# BLE_v1_0_prater_mod.net
KiCad netlist of a schematic drawn in EAGLE
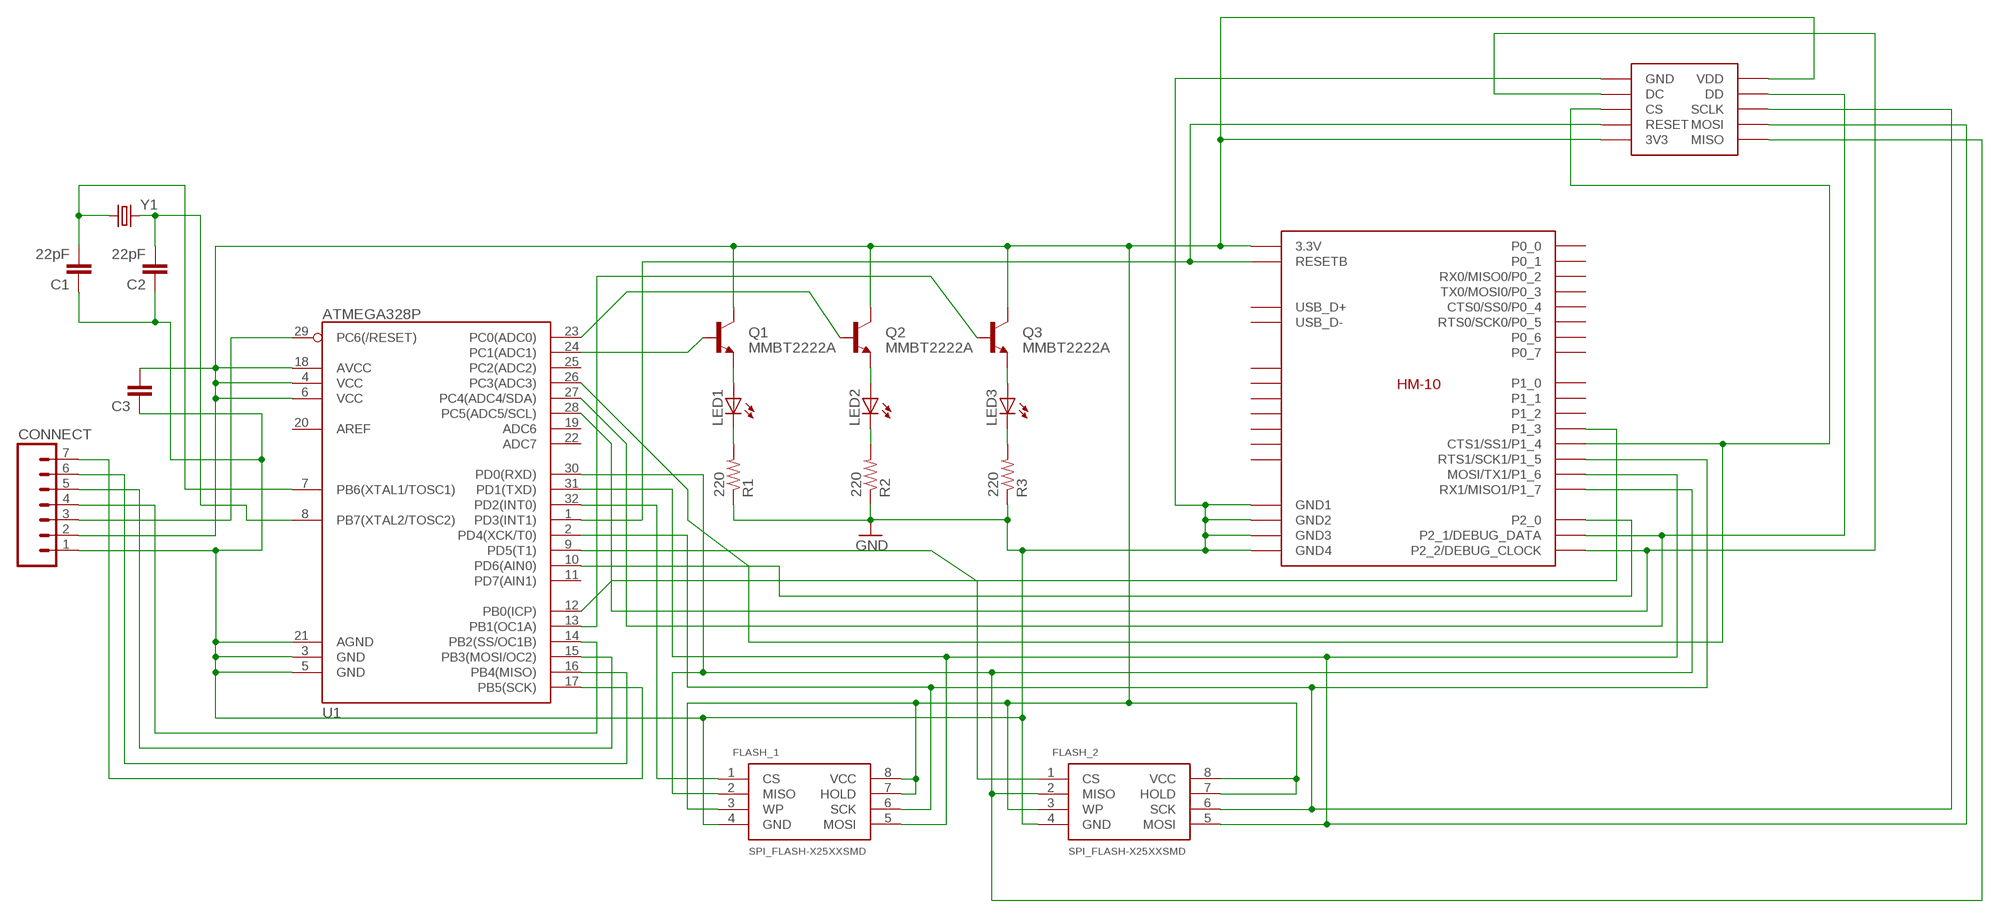
[diagram p0: schematic, sheet 1]

(export (version "E")
  (design (tool "Eeschema 10.0.6"))
  (components
    (comp (ref "C1")
      (value "22pF")
      (footprint "eagle-import:0603-CAP")
      (libsource (lib "eagle-import") (part "22PF-50V-5%(0603)"))
    )
    (comp (ref "C2")
      (value "22pF")
      (footprint "eagle-import:0603-CAP")
      (libsource (lib "eagle-import") (part "22PF-50V-5%(0603)"))
    )
    (comp (ref "C3")
      (value "CAP1210")
      (footprint "eagle-import:1210")
      (libsource (lib "eagle-import") (part "CAP1210"))
    )
    (comp (ref "CONNECT")
      (value "M07")
      (footprint "eagle-import:1X07")
      (libsource (lib "eagle-import") (part "M07"))
    )
    (comp (ref "FLASH_1")
      (value "SPI_FLASH-X25XXSMD")
      (footprint "eagle-import:SO08")
      (libsource (lib "eagle-import") (part "SPI_FLASH-X25XXSMD"))
    )
    (comp (ref "FLASH_2")
      (value "SPI_FLASH-X25XXSMD")
      (footprint "eagle-import:SO08")
      (libsource (lib "eagle-import") (part "SPI_FLASH-X25XXSMD"))
    )
    (comp (ref "LED1")
      (value "LED0603")
      (footprint "eagle-import:LED-0603")
      (libsource (lib "eagle-import") (part "LED0603"))
    )
    (comp (ref "LED2")
      (value "LED0603")
      (footprint "eagle-import:LED-0603")
      (libsource (lib "eagle-import") (part "LED0603"))
    )
    (comp (ref "LED3")
      (value "LED0603")
      (footprint "eagle-import:LED-0603")
      (libsource (lib "eagle-import") (part "LED0603"))
    )
    (comp (ref "Q1")
      (value "MMBT2222A")
      (footprint "eagle-import:SOT23")
      (libsource (lib "eagle-import") (part "TRANSISTOR_NPNMMBT2222A"))
    )
    (comp (ref "Q2")
      (value "MMBT2222A")
      (footprint "eagle-import:SOT23")
      (libsource (lib "eagle-import") (part "TRANSISTOR_NPNMMBT2222A"))
    )
    (comp (ref "Q3")
      (value "MMBT2222A")
      (footprint "eagle-import:SOT23")
      (libsource (lib "eagle-import") (part "TRANSISTOR_NPNMMBT2222A"))
    )
    (comp (ref "R1")
      (value "220")
      (footprint "eagle-import:M0805")
      (libsource (lib "eagle-import") (part "R-US_M0805"))
    )
    (comp (ref "R2")
      (value "220")
      (footprint "eagle-import:M0805")
      (libsource (lib "eagle-import") (part "R-US_M0805"))
    )
    (comp (ref "R3")
      (value "220")
      (footprint "eagle-import:M0805")
      (libsource (lib "eagle-import") (part "R-US_M0805"))
    )
    (comp (ref "U$1")
      (value "BLE-HM-10")
      (footprint "eagle-import:BLE-HM-10")
      (libsource (lib "eagle-import") (part "BLE-HM-10"))
    )
    (comp (ref "U$4")
      (value "2X5-.127-HEADER")
      (footprint "eagle-import:2X5-.127-HEADER")
      (libsource (lib "eagle-import") (part "2X5-.127-HEADER"))
    )
    (comp (ref "U1")
      (value "ATMEGA328P")
      (footprint "eagle-import:TQFP32-08")
      (libsource (lib "eagle-import") (part "ATMEGA328_SMT"))
    )
    (comp (ref "Y1")
      (value "CRYSTALHC49US")
      (footprint "eagle-import:HC49US")
      (libsource (lib "eagle-import") (part "CRYSTALHC49US"))
    )
  )
  (nets
    (net (code "1") (name "GND") (class "Default")
      (node (ref "C1") (pin "1") (pinfunction "1_1") (pintype "passive"))
      (node (ref "C2") (pin "1") (pinfunction "1_1") (pintype "passive"))
      (node (ref "C3") (pin "1") (pinfunction "1_1") (pintype "passive"))
      (node (ref "CONNECT") (pin "1") (pinfunction "1_1") (pintype "passive"))
      (node (ref "FLASH_1") (pin "4") (pinfunction "GND_4") (pintype "bidirectional"))
      (node (ref "FLASH_2") (pin "4") (pinfunction "GND_4") (pintype "bidirectional"))
      (node (ref "R1") (pin "1") (pinfunction "1_1") (pintype "passive"))
      (node (ref "R2") (pin "1") (pinfunction "1_1") (pintype "passive"))
      (node (ref "R3") (pin "1") (pinfunction "1_1") (pintype "passive"))
      (node (ref "U$1") (pin "GND1") (pinfunction "GND1_GND1") (pintype "bidirectional"))
      (node (ref "U$1") (pin "GND2") (pinfunction "GND2_GND2") (pintype "bidirectional"))
      (node (ref "U$1") (pin "GND3") (pinfunction "GND3_GND3") (pintype "bidirectional"))
      (node (ref "U$1") (pin "GND4") (pinfunction "GND4_GND4") (pintype "bidirectional"))
      (node (ref "U$4") (pin "GND") (pinfunction "GND_GND") (pintype "bidirectional"))
      (node (ref "U1") (pin "21") (pinfunction "AGND_21") (pintype "bidirectional"))
      (node (ref "U1") (pin "3") (pinfunction "GND_3") (pintype "bidirectional"))
      (node (ref "U1") (pin "5") (pinfunction "GND_5") (pintype "bidirectional"))
    )
    (net (code "2") (name "Net-(FLASH_1-CS)") (class "Default")
      (node (ref "FLASH_1") (pin "1") (pinfunction "CS_1") (pintype "bidirectional"))
      (node (ref "U1") (pin "32") (pinfunction "PD2(INT0)_32") (pintype "bidirectional"))
    )
    (net (code "3") (name "Net-(FLASH_1-HOLD)") (class "Default")
      (node (ref "C3") (pin "2") (pinfunction "2_2") (pintype "passive"))
      (node (ref "CONNECT") (pin "2") (pinfunction "2_2") (pintype "passive"))
      (node (ref "FLASH_1") (pin "3") (pinfunction "WP_3") (pintype "bidirectional"))
      (node (ref "FLASH_1") (pin "7") (pinfunction "HOLD_7") (pintype "bidirectional"))
      (node (ref "FLASH_1") (pin "8") (pinfunction "VCC_8") (pintype "bidirectional"))
      (node (ref "FLASH_2") (pin "3") (pinfunction "WP_3") (pintype "bidirectional"))
      (node (ref "FLASH_2") (pin "7") (pinfunction "HOLD_7") (pintype "bidirectional"))
      (node (ref "FLASH_2") (pin "8") (pinfunction "VCC_8") (pintype "bidirectional"))
      (node (ref "Q1") (pin "3") (pinfunction "C_3") (pintype "passive"))
      (node (ref "Q2") (pin "3") (pinfunction "C_3") (pintype "passive"))
      (node (ref "Q3") (pin "3") (pinfunction "C_3") (pintype "passive"))
      (node (ref "U$1") (pin "3.3V") (pinfunction "3.3V_3.3V") (pintype "bidirectional"))
      (node (ref "U$4") (pin "3V3") (pinfunction "3V3_3V3") (pintype "bidirectional"))
      (node (ref "U$4") (pin "VDD") (pinfunction "VDD_VDD") (pintype "bidirectional"))
      (node (ref "U1") (pin "18") (pinfunction "AVCC_18") (pintype "bidirectional"))
      (node (ref "U1") (pin "4") (pinfunction "VCC_4") (pintype "bidirectional"))
      (node (ref "U1") (pin "6") (pinfunction "VCC_6") (pintype "bidirectional"))
    )
    (net (code "4") (name "Net-(FLASH_1-MISO)") (class "Default")
      (node (ref "FLASH_1") (pin "2") (pinfunction "MISO_2") (pintype "bidirectional"))
      (node (ref "FLASH_2") (pin "2") (pinfunction "MISO_2") (pintype "bidirectional"))
      (node (ref "U$1") (pin "UART_RX") (pinfunction "RX1/MISO1/P1_7_UART_RX") (pintype "bidirectional"))
      (node (ref "U$4") (pin "MISO") (pinfunction "MISO_MISO") (pintype "bidirectional"))
      (node (ref "U1") (pin "30") (pinfunction "PD0(RXD)_30") (pintype "bidirectional"))
    )
    (net (code "5") (name "Net-(FLASH_1-MOSI)") (class "Default")
      (node (ref "FLASH_1") (pin "5") (pinfunction "MOSI_5") (pintype "bidirectional"))
      (node (ref "FLASH_2") (pin "5") (pinfunction "MOSI_5") (pintype "bidirectional"))
      (node (ref "U$1") (pin "UART_TX") (pinfunction "MOSI/TX1/P1_6_UART_TX") (pintype "bidirectional"))
      (node (ref "U$4") (pin "MOSI") (pinfunction "MOSI_MOSI") (pintype "bidirectional"))
      (node (ref "U1") (pin "31") (pinfunction "PD1(TXD)_31") (pintype "bidirectional"))
    )
    (net (code "6") (name "Net-(FLASH_1-SCK)") (class "Default")
      (node (ref "FLASH_1") (pin "6") (pinfunction "SCK_6") (pintype "bidirectional"))
      (node (ref "FLASH_2") (pin "6") (pinfunction "SCK_6") (pintype "bidirectional"))
      (node (ref "U$1") (pin "UART_RTS") (pinfunction "RTS1/SCK1/P1_5_UART_RTS") (pintype "bidirectional"))
      (node (ref "U$4") (pin "SCLK") (pinfunction "SCLK_SCLK") (pintype "bidirectional"))
      (node (ref "U1") (pin "2") (pinfunction "PD4(XCK/T0)_2") (pintype "bidirectional"))
    )
    (net (code "7") (name "Net-(FLASH_2-CS)") (class "Default")
      (node (ref "FLASH_2") (pin "1") (pinfunction "CS_1") (pintype "bidirectional"))
      (node (ref "U1") (pin "9") (pinfunction "PD5(T1)_9") (pintype "bidirectional"))
    )
    (net (code "8") (name "Net-(LED1-PadC)") (class "Default")
      (node (ref "LED1") (pin "C") (pinfunction "C_C") (pintype "passive"))
      (node (ref "R1") (pin "2") (pinfunction "2_2") (pintype "passive"))
    )
    (net (code "9") (name "Net-(LED2-PadC)") (class "Default")
      (node (ref "LED2") (pin "C") (pinfunction "C_C") (pintype "passive"))
      (node (ref "R2") (pin "2") (pinfunction "2_2") (pintype "passive"))
    )
    (net (code "10") (name "Net-(LED3-PadC)") (class "Default")
      (node (ref "LED3") (pin "C") (pinfunction "C_C") (pintype "passive"))
      (node (ref "R3") (pin "2") (pinfunction "2_2") (pintype "passive"))
    )
    (net (code "11") (name "Net-(Q1-B)") (class "Default")
      (node (ref "Q1") (pin "1") (pinfunction "B_1") (pintype "passive"))
      (node (ref "U1") (pin "24") (pinfunction "PC1(ADC1)_24") (pintype "bidirectional"))
    )
    (net (code "12") (name "Net-(Q1-E)") (class "Default")
      (node (ref "LED1") (pin "A") (pinfunction "A_A") (pintype "passive"))
      (node (ref "Q1") (pin "2") (pinfunction "E_2") (pintype "passive"))
    )
    (net (code "13") (name "Net-(Q2-B)") (class "Default")
      (node (ref "Q2") (pin "1") (pinfunction "B_1") (pintype "passive"))
      (node (ref "U1") (pin "23") (pinfunction "PC0(ADC0)_23") (pintype "bidirectional"))
    )
    (net (code "14") (name "Net-(Q2-E)") (class "Default")
      (node (ref "LED2") (pin "A") (pinfunction "A_A") (pintype "passive"))
      (node (ref "Q2") (pin "2") (pinfunction "E_2") (pintype "passive"))
    )
    (net (code "15") (name "Net-(Q3-B)") (class "Default")
      (node (ref "Q3") (pin "1") (pinfunction "B_1") (pintype "passive"))
      (node (ref "U1") (pin "13") (pinfunction "PB1(OC1A)_13") (pintype "bidirectional"))
    )
    (net (code "16") (name "Net-(Q3-E)") (class "Default")
      (node (ref "LED3") (pin "A") (pinfunction "A_A") (pintype "passive"))
      (node (ref "Q3") (pin "2") (pinfunction "E_2") (pintype "passive"))
    )
    (net (code "17") (name "Net-(U$1-CTS1{slash}SS1{slash}P1_4)") (class "Default")
      (node (ref "U$1") (pin "UART_CTS") (pinfunction "CTS1/SS1/P1_4_UART_CTS") (pintype "bidirectional"))
      (node (ref "U$4") (pin "CS") (pinfunction "CS_CS") (pintype "bidirectional"))
      (node (ref "U1") (pin "26") (pinfunction "PC3(ADC3)_26") (pintype "bidirectional"))
    )
    (net (code "18") (name "Net-(U$1-P1_3)") (class "Default")
      (node (ref "U$1") (pin "PIO0") (pinfunction "P1_3_PIO0") (pintype "bidirectional"))
      (node (ref "U1") (pin "12") (pinfunction "PB0(ICP)_12") (pintype "bidirectional"))
    )
    (net (code "19") (name "Net-(U$1-P2_0)") (class "Default")
      (node (ref "U$1") (pin "AIO0") (pinfunction "P2_0_AIO0") (pintype "bidirectional"))
      (node (ref "U1") (pin "10") (pinfunction "PD6(AIN0)_10") (pintype "bidirectional"))
    )
    (net (code "20") (name "Net-(U$1-P2_1{slash}DEBUG_DATA)") (class "Default")
      (node (ref "U$1") (pin "PCM_SYNC") (pinfunction "P2_1/DEBUG_DATA_PCM_SYNC") (pintype "bidirectional"))
      (node (ref "U$4") (pin "DD") (pinfunction "DD_DD") (pintype "bidirectional"))
      (node (ref "U1") (pin "27") (pinfunction "PC4(ADC4/SDA)_27") (pintype "bidirectional"))
    )
    (net (code "21") (name "Net-(U$1-P2_2{slash}DEBUG_CLOCK)") (class "Default")
      (node (ref "U$1") (pin "PCM_IN") (pinfunction "P2_2/DEBUG_CLOCK_PCM_IN") (pintype "bidirectional"))
      (node (ref "U$4") (pin "DC") (pinfunction "DC_DC") (pintype "bidirectional"))
      (node (ref "U1") (pin "28") (pinfunction "PC5(ADC5/SCL)_28") (pintype "bidirectional"))
    )
    (net (code "22") (name "Net-(U$1-RESETB)") (class "Default")
      (node (ref "U$1") (pin "RESET") (pinfunction "RESETB_RESET") (pintype "bidirectional"))
      (node (ref "U$4") (pin "RESET") (pinfunction "RESET_RESET") (pintype "bidirectional"))
      (node (ref "U1") (pin "1") (pinfunction "PD3(INT1)_1") (pintype "bidirectional"))
    )
    (net (code "23") (name "Net-(U1-PB2(SS{slash}OC1B))") (class "Default")
      (node (ref "CONNECT") (pin "4") (pinfunction "4_4") (pintype "passive"))
      (node (ref "U1") (pin "14") (pinfunction "PB2(SS/OC1B)_14") (pintype "bidirectional"))
    )
    (net (code "24") (name "Net-(U1-PB3(MOSI{slash}OC2))") (class "Default")
      (node (ref "CONNECT") (pin "5") (pinfunction "5_5") (pintype "passive"))
      (node (ref "U1") (pin "15") (pinfunction "PB3(MOSI/OC2)_15") (pintype "bidirectional"))
    )
    (net (code "25") (name "Net-(U1-PB4(MISO))") (class "Default")
      (node (ref "CONNECT") (pin "6") (pinfunction "6_6") (pintype "passive"))
      (node (ref "U1") (pin "16") (pinfunction "PB4(MISO)_16") (pintype "bidirectional"))
    )
    (net (code "26") (name "Net-(U1-PB5(SCK))") (class "Default")
      (node (ref "CONNECT") (pin "7") (pinfunction "7_7") (pintype "passive"))
      (node (ref "U1") (pin "17") (pinfunction "PB5(SCK)_17") (pintype "bidirectional"))
    )
    (net (code "27") (name "Net-(U1-PB6(XTAL1{slash}TOSC1))") (class "Default")
      (node (ref "C1") (pin "2") (pinfunction "2_2") (pintype "passive"))
      (node (ref "U1") (pin "7") (pinfunction "PB6(XTAL1/TOSC1)_7") (pintype "bidirectional"))
      (node (ref "Y1") (pin "1") (pinfunction "1_1") (pintype "passive"))
    )
    (net (code "28") (name "Net-(U1-PB7(XTAL2{slash}TOSC2))") (class "Default")
      (node (ref "C2") (pin "2") (pinfunction "2_2") (pintype "passive"))
      (node (ref "U1") (pin "8") (pinfunction "PB7(XTAL2/TOSC2)_8") (pintype "bidirectional"))
      (node (ref "Y1") (pin "2") (pinfunction "2_2") (pintype "passive"))
    )
    (net (code "29") (name "Net-(U1-PC6({slash}RESET))") (class "Default")
      (node (ref "CONNECT") (pin "3") (pinfunction "3_3") (pintype "passive"))
      (node (ref "U1") (pin "29") (pinfunction "PC6(/RESET)_29") (pintype "bidirectional"))
    )
    (net (code "30") (name "unconnected-(U$1-CTS0{slash}SS0{slash}P0_4-PadPIO7)") (class "Default")
      (node (ref "U$1") (pin "PIO7") (pinfunction "CTS0/SS0/P0_4_PIO7") (pintype "bidirectional"))
    )
    (net (code "31") (name "unconnected-(U$1-P0_0-PadPIO11)") (class "Default")
      (node (ref "U$1") (pin "PIO11") (pinfunction "P0_0_PIO11") (pintype "bidirectional"))
    )
    (net (code "32") (name "unconnected-(U$1-P0_1-PadPIO10)") (class "Default")
      (node (ref "U$1") (pin "PIO10") (pinfunction "P0_1_PIO10") (pintype "bidirectional"))
    )
    (net (code "33") (name "unconnected-(U$1-P0_6-PadPIO5)") (class "Default")
      (node (ref "U$1") (pin "PIO5") (pinfunction "P0_6_PIO5") (pintype "bidirectional"))
    )
    (net (code "34") (name "unconnected-(U$1-P0_7-PadPIO4)") (class "Default")
      (node (ref "U$1") (pin "PIO4") (pinfunction "P0_7_PIO4") (pintype "bidirectional"))
    )
    (net (code "35") (name "unconnected-(U$1-P1_0-PadPIO3)") (class "Default")
      (node (ref "U$1") (pin "PIO3") (pinfunction "P1_0_PIO3") (pintype "bidirectional"))
    )
    (net (code "36") (name "unconnected-(U$1-P1_1-PadPIO2)") (class "Default")
      (node (ref "U$1") (pin "PIO2") (pinfunction "P1_1_PIO2") (pintype "bidirectional"))
    )
    (net (code "37") (name "unconnected-(U$1-P1_2-PadPIO1)") (class "Default")
      (node (ref "U$1") (pin "PIO1") (pinfunction "P1_2_PIO1") (pintype "bidirectional"))
    )
    (net (code "38") (name "unconnected-(U$1-PadAIO1)") (class "Default")
      (node (ref "U$1") (pin "AIO1") (pinfunction "AIO1_AIO1") (pintype "bidirectional"))
    )
    (net (code "39") (name "unconnected-(U$1-PadPCM_CLK)") (class "Default")
      (node (ref "U$1") (pin "PCM_CLK") (pinfunction "PCM_CLK_PCM_CLK") (pintype "bidirectional"))
    )
    (net (code "40") (name "unconnected-(U$1-PadPCM_OUT)") (class "Default")
      (node (ref "U$1") (pin "PCM_OUT") (pinfunction "PCM_OUT_PCM_OUT") (pintype "bidirectional"))
    )
    (net (code "41") (name "unconnected-(U$1-PadSPI_CLK)") (class "Default")
      (node (ref "U$1") (pin "SPI_CLK") (pinfunction "SPI_CLK_SPI_CLK") (pintype "bidirectional"))
    )
    (net (code "42") (name "unconnected-(U$1-PadSPI_CSB)") (class "Default")
      (node (ref "U$1") (pin "SPI_CSB") (pinfunction "SPI_CSB_SPI_CSB") (pintype "bidirectional"))
    )
    (net (code "43") (name "unconnected-(U$1-PadSPI_MISO)") (class "Default")
      (node (ref "U$1") (pin "SPI_MISO") (pinfunction "SPI_MISO_SPI_MISO") (pintype "bidirectional"))
    )
    (net (code "44") (name "unconnected-(U$1-PadSPI_MOSI)") (class "Default")
      (node (ref "U$1") (pin "SPI_MOSI") (pinfunction "SPI_MOSI_SPI_MOSI") (pintype "bidirectional"))
    )
    (net (code "45") (name "unconnected-(U$1-PadUSB_D+)") (class "Default")
      (node (ref "U$1") (pin "USB_D+") (pinfunction "USB_D+_USB_D+") (pintype "bidirectional"))
    )
    (net (code "46") (name "unconnected-(U$1-PadUSB_D-)") (class "Default")
      (node (ref "U$1") (pin "USB_D-") (pinfunction "USB_D-_USB_D-") (pintype "bidirectional"))
    )
    (net (code "47") (name "unconnected-(U$1-RTS0{slash}SCK0{slash}P0_5-PadPIO6)") (class "Default")
      (node (ref "U$1") (pin "PIO6") (pinfunction "RTS0/SCK0/P0_5_PIO6") (pintype "bidirectional"))
    )
    (net (code "48") (name "unconnected-(U$1-RX0{slash}MISO0{slash}P0_2-PadPIO9)") (class "Default")
      (node (ref "U$1") (pin "PIO9") (pinfunction "RX0/MISO0/P0_2_PIO9") (pintype "bidirectional"))
    )
    (net (code "49") (name "unconnected-(U$1-TX0{slash}MOSI0{slash}P0_3-PadPIO8)") (class "Default")
      (node (ref "U$1") (pin "PIO8") (pinfunction "TX0/MOSI0/P0_3_PIO8") (pintype "bidirectional"))
    )
    (net (code "50") (name "unconnected-(U1-ADC6-Pad19)") (class "Default")
      (node (ref "U1") (pin "19") (pinfunction "ADC6_19") (pintype "bidirectional"))
    )
    (net (code "51") (name "unconnected-(U1-ADC7-Pad22)") (class "Default")
      (node (ref "U1") (pin "22") (pinfunction "ADC7_22") (pintype "bidirectional"))
    )
    (net (code "52") (name "unconnected-(U1-AREF-Pad20)") (class "Default")
      (node (ref "U1") (pin "20") (pinfunction "AREF_20") (pintype "bidirectional"))
    )
    (net (code "53") (name "unconnected-(U1-PC2(ADC2)-Pad25)") (class "Default")
      (node (ref "U1") (pin "25") (pinfunction "PC2(ADC2)_25") (pintype "bidirectional"))
    )
    (net (code "54") (name "unconnected-(U1-PD7(AIN1)-Pad11)") (class "Default")
      (node (ref "U1") (pin "11") (pinfunction "PD7(AIN1)_11") (pintype "bidirectional"))
    )
  )
)
